# SBG.net
KiCad netlist of a schematic drawn in Altium Designer
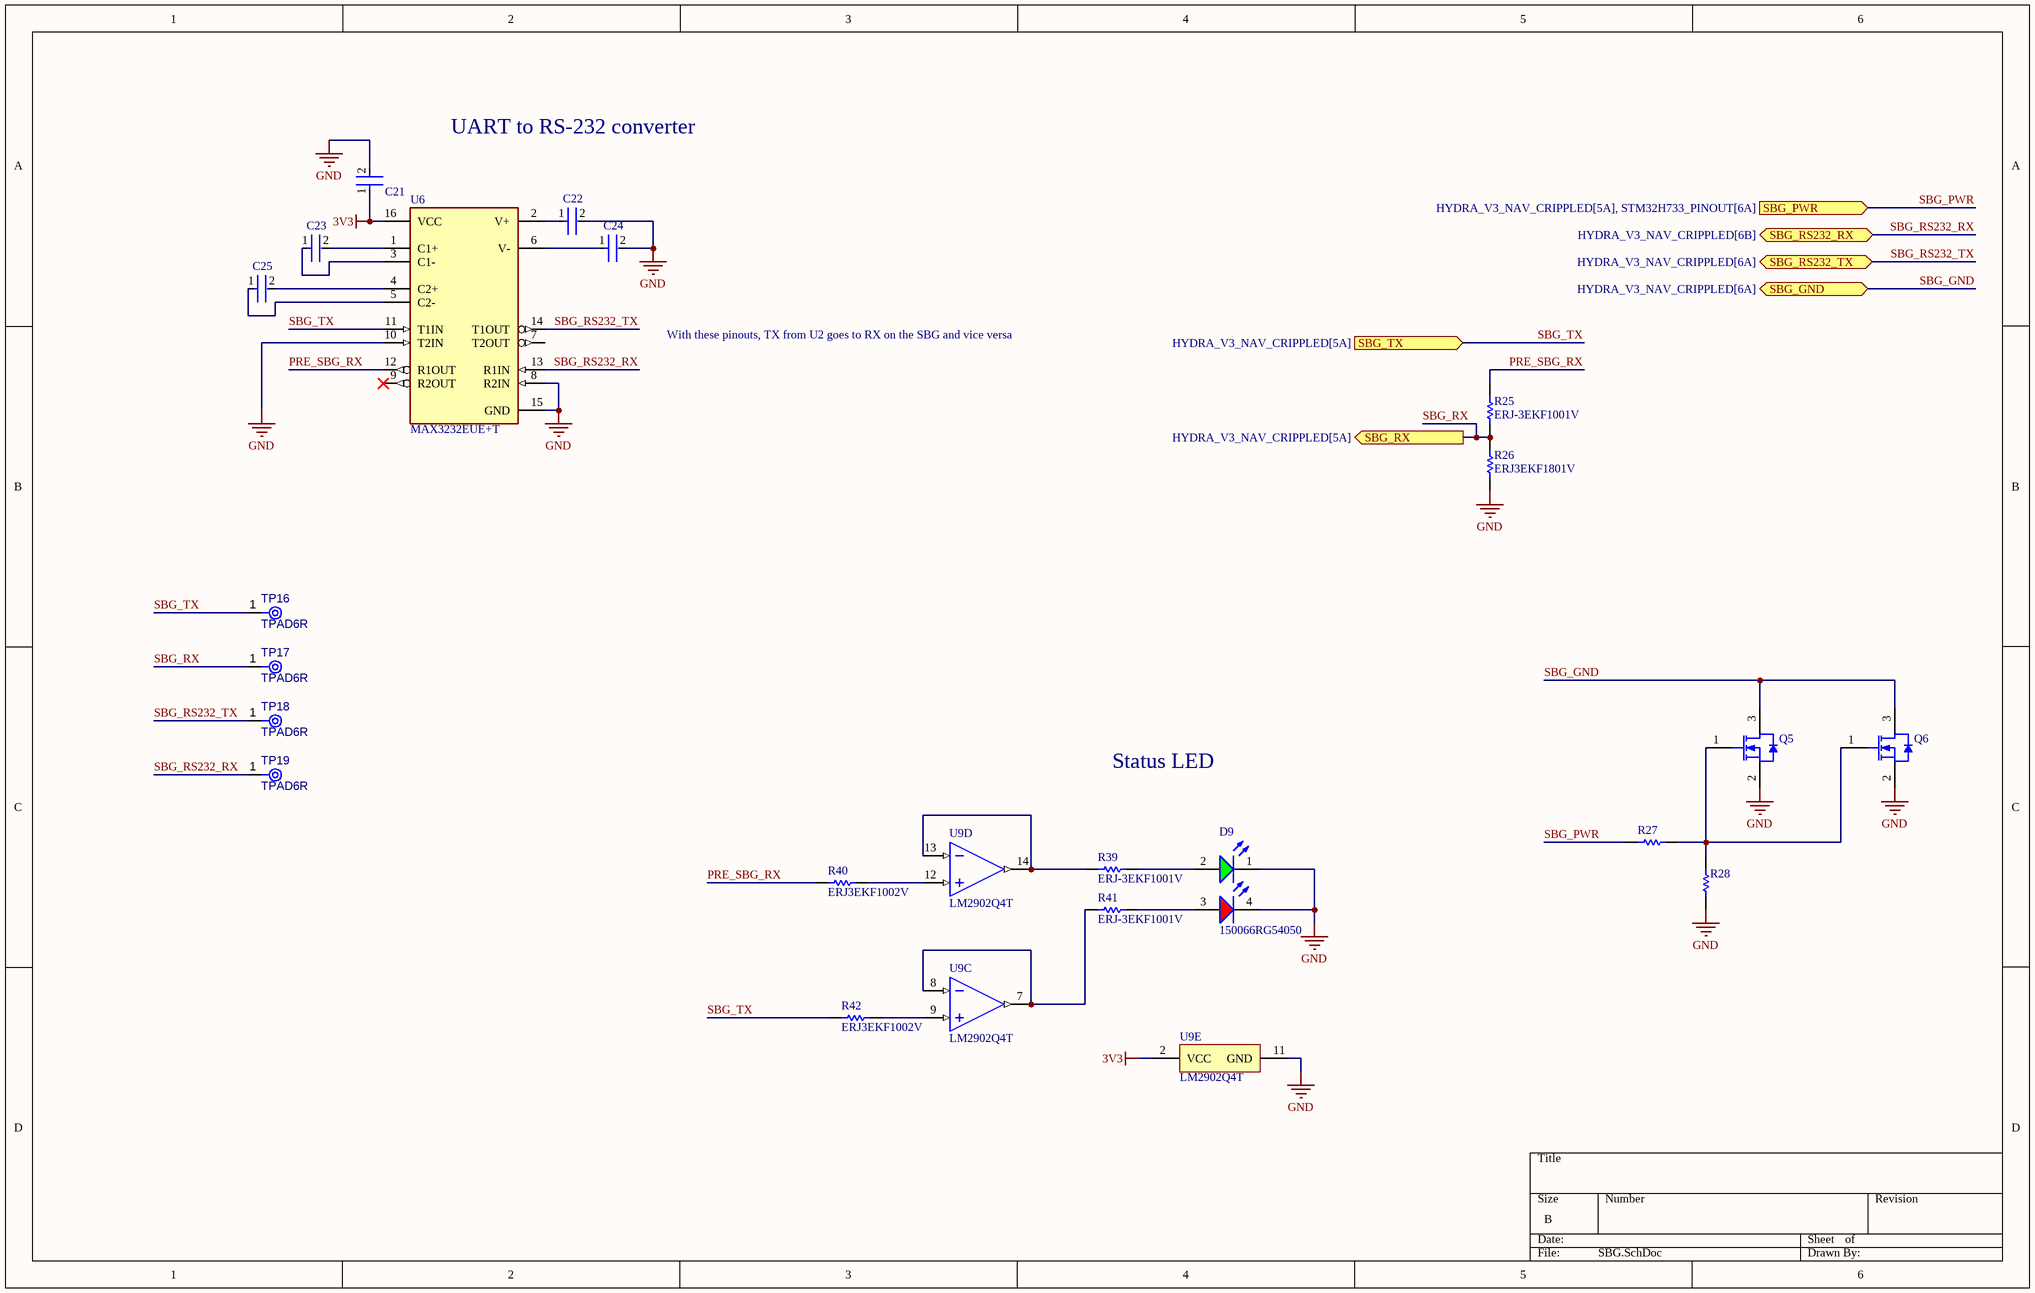
[diagram p0: SBG.SchDoc]

(export (version "E")
  (design (tool "Eeschema 10.0.6"))
  (components
    (comp (ref "C21")
      (value "C0402C104K8PACTU")
      (footprint "FP-C0402-BB-MFG")
      (description "CAP CER 0.1UF 10V X5R 0402")
      (fields (field (name "MANUFACTURER") "Kemet") (field (name "TOLERANCE") "0.1"))
      (libsource (lib "Altium Content Vault") (part "b4654b650e69147ec39a6b967a45e02"))
    )
    (comp (ref "C22")
      (value "C0603X104K5RACTU")
      (footprint "FP-C0603-CJ-MFG")
      (description "CAP CER 0.1UF 50V X7R 0603")
      (fields (field (name "VOLTAGE") "50V") (field (name "MANUFACTURER") "Kemet"))
      (libsource (lib "Altium Content Vault") (part "11868f565c42a9108669ba33697ecf6"))
    )
    (comp (ref "C23")
      (value "C0603X104K5RACTU")
      (footprint "FP-C0603-CJ-MFG")
      (description "CAP CER 0.1UF 50V X7R 0603")
      (fields (field (name "VOLTAGE") "50V") (field (name "MANUFACTURER") "Kemet"))
      (libsource (lib "Altium Content Vault") (part "11868f565c42a9108669ba33697ecf6"))
    )
    (comp (ref "C24")
      (value "C0603X104K5RACTU")
      (footprint "FP-C0603-CJ-MFG")
      (description "CAP CER 0.1UF 50V X7R 0603")
      (fields (field (name "VOLTAGE") "50V") (field (name "MANUFACTURER") "Kemet"))
      (libsource (lib "Altium Content Vault") (part "11868f565c42a9108669ba33697ecf6"))
    )
    (comp (ref "C25")
      (value "C0603X104K5RACTU")
      (footprint "FP-C0603-CJ-MFG")
      (description "CAP CER 0.1UF 50V X7R 0603")
      (fields (field (name "VOLTAGE") "50V") (field (name "MANUFACTURER") "Kemet"))
      (libsource (lib "Altium Content Vault") (part "11868f565c42a9108669ba33697ecf6"))
    )
    (comp (ref "D9")
      (value "150066RG54050")
      (footprint "WL-SBCD_0606")
      (description "Led, Red/Grn, 180Mcd/230Mcd, 624Nm/525Nm Rohs Compliant: Yes")
      (libsource (lib "uORocketry Hardware") (part "WL-SBCD_0606_Red & Green"))
    )
    (comp (ref "Q5")
      (value "BSS138W-7-F")
      (footprint "DIOD-SOT323-3_V")
      (fields (field (name "MANUFACTURER") "DiodesIncorporated"))
      (libsource (lib "Altium Content Vault") (part "NEMOS-GSD-3"))
    )
    (comp (ref "Q6")
      (value "BSS138W-7-F")
      (footprint "DIOD-SOT323-3_V")
      (fields (field (name "MANUFACTURER") "DiodesIncorporated"))
      (libsource (lib "Altium Content Vault") (part "NEMOS-GSD-3"))
    )
    (comp (ref "R25")
      (value "ERJ-3EKF1001V")
      (footprint "RESC1608X55X30LL15T15")
      (fields (field (name "MANUFACTURER") "Panasonic"))
      (libsource (lib "Altium Content Vault") (part "RES"))
    )
    (comp (ref "R26")
      (value "ERJ3EKF1801V")
      (footprint "RESC1608X55X30LL15T15")
      (fields (field (name "MANUFACTURER") "Panasonic"))
      (libsource (lib "Altium Content Vault") (part "RES"))
    )
    (comp (ref "R27")
      (value "ERJ-3EKF1001V")
      (footprint "RESC1608X55X30LL15T15")
      (fields (field (name "MANUFACTURER") "Panasonic"))
      (libsource (lib "Altium Content Vault") (part "RES"))
    )
    (comp (ref "R28")
      (value "ERJ3EKF1002V")
      (footprint "RESC1609X55X30LL15T15")
      (description "Chip Resistor, 10 KOhm, +/- 1%, 0.1 W, -55 to 155 degC, 0603 (1608 Metric), RoHS, Tape and Reel")
      (fields (field (name "TOLERANCE") "1%") (field (name "MANUFACTURER") "Panasonic"))
      (libsource (lib "Altium Content Vault") (part "RES-2"))
    )
    (comp (ref "R39")
      (value "ERJ-3EKF1001V")
      (footprint "RESC1608X55X30LL15T15")
      (fields (field (name "MANUFACTURER") "Panasonic"))
      (libsource (lib "Altium Content Vault") (part "RES"))
    )
    (comp (ref "R40")
      (value "ERJ3EKF1002V")
      (footprint "RESC1609X55X30LL15T15")
      (description "Chip Resistor, 10 KOhm, +/- 1%, 0.1 W, -55 to 155 degC, 0603 (1608 Metric), RoHS, Tape and Reel")
      (fields (field (name "TOLERANCE") "1%") (field (name "MANUFACTURER") "Panasonic"))
      (libsource (lib "Altium Content Vault") (part "RES-2"))
    )
    (comp (ref "R41")
      (value "ERJ-3EKF1001V")
      (footprint "RESC1608X55X30LL15T15")
      (fields (field (name "MANUFACTURER") "Panasonic"))
      (libsource (lib "Altium Content Vault") (part "RES"))
    )
    (comp (ref "R42")
      (value "ERJ3EKF1002V")
      (footprint "RESC1609X55X30LL15T15")
      (description "Chip Resistor, 10 KOhm, +/- 1%, 0.1 W, -55 to 155 degC, 0603 (1608 Metric), RoHS, Tape and Reel")
      (fields (field (name "TOLERANCE") "1%") (field (name "MANUFACTURER") "Panasonic"))
      (libsource (lib "Altium Content Vault") (part "RES-2"))
    )
    (comp (ref "TP16")
      (value "TPAD6R")
      (footprint "TP06R")
      (description "0.6mm round")
      (libsource (lib "uORocketry Hardware") (part "CMP-001-0001-4"))
    )
    (comp (ref "TP17")
      (value "TPAD6R")
      (footprint "TP06R")
      (description "0.6mm round")
      (libsource (lib "uORocketry Hardware") (part "CMP-001-0001-4"))
    )
    (comp (ref "TP18")
      (value "TPAD6R")
      (footprint "TP06R")
      (description "0.6mm round")
      (libsource (lib "uORocketry Hardware") (part "CMP-001-0001-4"))
    )
    (comp (ref "TP19")
      (value "TPAD6R")
      (footprint "TP06R")
      (description "0.6mm round")
      (libsource (lib "uORocketry Hardware") (part "CMP-001-0001-4"))
    )
    (comp (ref "U6")
      (value "MAX3232EUE+T")
      (footprint "FP-U16-1-MFG")
      (description "IC TXRX RS-232 LP 16-TSSOP")
      (fields
        (field (name "OCTOPART") "https://octopart.com/max3232eue%2Bt-maxim+integrated-39814427")
        (field (name "MANUFACTURER") "Maxim Integrated")
      )
      (libsource (lib "Altium Content Vault") (part "753fb76a544055c619a09297c280b9d"))
    )
    (comp (ref "U9")
      (value "LM2902Q4T")
      (footprint "LM2902Q4T-Footprint-1")
      (description "LM2902 Series 30 V 1.3 MHz Low-Power Quad Operational Amplifier - QFN-16 (3x3)")
      (libsource (lib "uORocketry Hardware") (part "LM2902Q4T"))
    )
  )
  (nets
    (net (code "1") (name "/PRE_SBG_RX") (class "Default")
      (node (ref "R25") (pin "2") (pinfunction "2_2") (pintype "passive"))
      (node (ref "R40") (pin "1") (pinfunction "1_1") (pintype "passive"))
      (node (ref "U6") (pin "12") (pinfunction "R1OUT_12") (pintype "output"))
    )
    (net (code "2") (name "/SBG_GND") (class "Default")
      (node (ref "Q5") (pin "3") (pinfunction "D_3") (pintype "passive"))
      (node (ref "Q6") (pin "3") (pinfunction "D_3") (pintype "passive"))
    )
    (net (code "3") (name "/SBG_PWR") (class "Default")
      (node (ref "R27") (pin "1") (pinfunction "1_1") (pintype "passive"))
    )
    (net (code "4") (name "/SBG_RS232_RX") (class "Default")
      (node (ref "TP19") (pin "1") (pinfunction "TP_1") (pintype "passive"))
      (node (ref "U6") (pin "13") (pinfunction "R1IN_13") (pintype "input"))
    )
    (net (code "5") (name "/SBG_RS232_TX") (class "Default")
      (node (ref "TP18") (pin "1") (pinfunction "TP_1") (pintype "passive"))
      (node (ref "U6") (pin "14") (pinfunction "T1OUT_14") (pintype "output"))
    )
    (net (code "6") (name "/SBG_RX") (class "Default")
      (node (ref "R25") (pin "1") (pinfunction "1_1") (pintype "passive"))
      (node (ref "R26") (pin "2") (pinfunction "2_2") (pintype "passive"))
      (node (ref "TP17") (pin "1") (pinfunction "TP_1") (pintype "passive"))
    )
    (net (code "7") (name "/SBG_TX") (class "Default")
      (node (ref "R42") (pin "2") (pinfunction "2_2") (pintype "passive"))
      (node (ref "TP16") (pin "1") (pinfunction "TP_1") (pintype "passive"))
      (node (ref "U6") (pin "11") (pinfunction "T1IN_11") (pintype "input"))
    )
    (net (code "8") (name "3V3") (class "Default")
      (node (ref "C21") (pin "1") (pinfunction "1_1") (pintype "passive"))
      (node (ref "U6") (pin "16") (pinfunction "VCC_16") (pintype "power_in"))
      (node (ref "U9") (pin "2") (pinfunction "VCC_2") (pintype "power_in"))
    )
    (net (code "9") (name "GND") (class "Default")
      (node (ref "C21") (pin "2") (pinfunction "2_2") (pintype "passive"))
      (node (ref "C22") (pin "2") (pinfunction "2_2") (pintype "passive"))
      (node (ref "C24") (pin "2") (pinfunction "2_2") (pintype "passive"))
      (node (ref "D9") (pin "1") (pinfunction "K_1") (pintype "passive"))
      (node (ref "D9") (pin "4") (pinfunction "K_4") (pintype "passive"))
      (node (ref "Q5") (pin "2") (pinfunction "S_2") (pintype "passive"))
      (node (ref "Q6") (pin "2") (pinfunction "S_2") (pintype "passive"))
      (node (ref "R26") (pin "1") (pinfunction "1_1") (pintype "passive"))
      (node (ref "R28") (pin "1") (pinfunction "1_1") (pintype "passive"))
      (node (ref "U6") (pin "10") (pinfunction "T2IN_10") (pintype "input"))
      (node (ref "U6") (pin "15") (pinfunction "GND_15") (pintype "power_in"))
      (node (ref "U6") (pin "8") (pinfunction "R2IN_8") (pintype "input"))
      (node (ref "U9") (pin "11") (pinfunction "GND_11") (pintype "power_in"))
    )
    (net (code "10") (name "Net-(D9-A-Pad2)") (class "Default")
      (node (ref "D9") (pin "2") (pinfunction "A_2") (pintype "passive"))
      (node (ref "R39") (pin "2") (pinfunction "2_2") (pintype "passive"))
    )
    (net (code "11") (name "Net-(D9-A-Pad3)") (class "Default")
      (node (ref "D9") (pin "3") (pinfunction "A_3") (pintype "passive"))
      (node (ref "R41") (pin "2") (pinfunction "2_2") (pintype "passive"))
    )
    (net (code "12") (name "Net-(Q5-G)") (class "Default")
      (node (ref "Q5") (pin "1") (pinfunction "G_1") (pintype "passive"))
      (node (ref "Q6") (pin "1") (pinfunction "G_1") (pintype "passive"))
      (node (ref "R27") (pin "2") (pinfunction "2_2") (pintype "passive"))
      (node (ref "R28") (pin "2") (pinfunction "2_2") (pintype "passive"))
    )
    (net (code "13") (name "Net-(U6-C1+)") (class "Default")
      (node (ref "C23") (pin "2") (pinfunction "2_2") (pintype "passive"))
      (node (ref "U6") (pin "1") (pinfunction "C1+_1") (pintype "passive"))
    )
    (net (code "14") (name "Net-(U6-C1-)") (class "Default")
      (node (ref "C23") (pin "1") (pinfunction "1_1") (pintype "passive"))
      (node (ref "U6") (pin "3") (pinfunction "C1-_3") (pintype "passive"))
    )
    (net (code "15") (name "Net-(U6-C2+)") (class "Default")
      (node (ref "C25") (pin "2") (pinfunction "2_2") (pintype "passive"))
      (node (ref "U6") (pin "4") (pinfunction "C2+_4") (pintype "passive"))
    )
    (net (code "16") (name "Net-(U6-C2-)") (class "Default")
      (node (ref "C25") (pin "1") (pinfunction "1_1") (pintype "passive"))
      (node (ref "U6") (pin "5") (pinfunction "C2-_5") (pintype "passive"))
    )
    (net (code "17") (name "Net-(U6-V+)") (class "Default")
      (node (ref "C22") (pin "1") (pinfunction "1_1") (pintype "passive"))
      (node (ref "U6") (pin "2") (pinfunction "V+_2") (pintype "power_in"))
    )
    (net (code "18") (name "Net-(U6-V-)") (class "Default")
      (node (ref "C24") (pin "1") (pinfunction "1_1") (pintype "passive"))
      (node (ref "U6") (pin "6") (pinfunction "V-_6") (pintype "power_in"))
    )
    (net (code "19") (name "Net-(U9C-3IN+)") (class "Default")
      (node (ref "R42") (pin "1") (pinfunction "1_1") (pintype "passive"))
      (node (ref "U9") (pin "9") (pinfunction "3IN+_9") (pintype "input"))
    )
    (net (code "20") (name "Net-(U9C-3IN-)") (class "Default")
      (node (ref "R41") (pin "1") (pinfunction "1_1") (pintype "passive"))
      (node (ref "U9") (pin "7") (pinfunction "3OUT_7") (pintype "output"))
      (node (ref "U9") (pin "8") (pinfunction "3IN-_8") (pintype "input"))
    )
    (net (code "21") (name "Net-(U9D-4IN+)") (class "Default")
      (node (ref "R40") (pin "2") (pinfunction "2_2") (pintype "passive"))
      (node (ref "U9") (pin "12") (pinfunction "4IN+_12") (pintype "input"))
    )
    (net (code "22") (name "Net-(U9D-4IN-)") (class "Default")
      (node (ref "R39") (pin "1") (pinfunction "1_1") (pintype "passive"))
      (node (ref "U9") (pin "13") (pinfunction "4IN-_13") (pintype "input"))
      (node (ref "U9") (pin "14") (pinfunction "4OUT_14") (pintype "output"))
    )
    (net (code "23") (name "unconnected-(U6-R2OUT-Pad9)") (class "Default")
      (node (ref "U6") (pin "9") (pinfunction "R2OUT_9") (pintype "output+no_connect"))
    )
    (net (code "24") (name "unconnected-(U6-T2OUT-Pad7)") (class "Default")
      (node (ref "U6") (pin "7") (pinfunction "T2OUT_7") (pintype "output"))
    )
  )
)
